# Argo2_Tracker.net
KiCad netlist of a schematic drawn in EAGLE
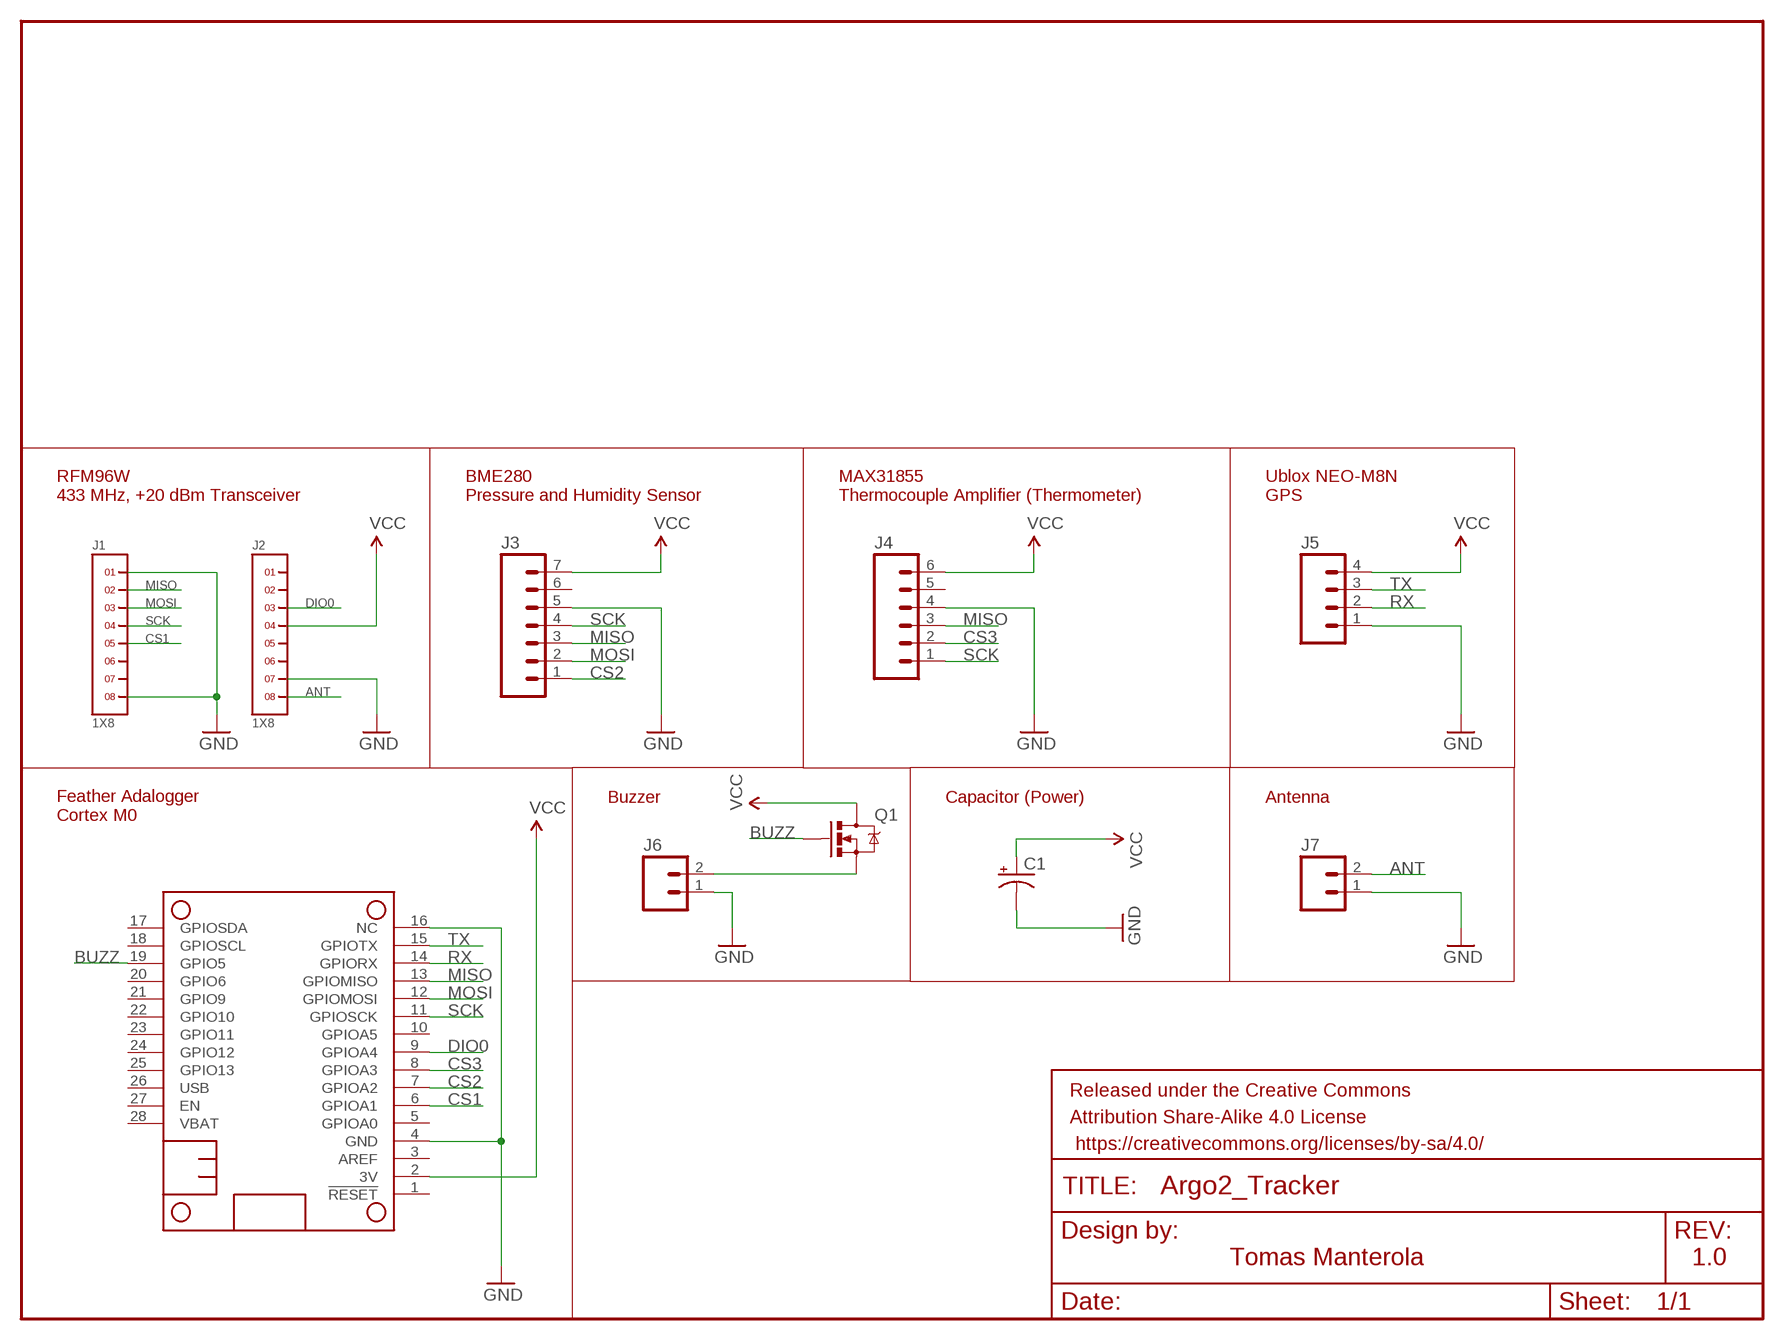
[diagram p0: schematic, sheet 1]

(export (version "E")
  (design (tool "Eeschema 10.0.6"))
  (components
    (comp (ref "C1")
      (value "CAP_POLPTH4")
      (footprint "eagle-import:CPOL-RADIAL-1000UF-25V")
      (libsource (lib "eagle-import") (part "CAP_POLPTH4"))
    )
    (comp (ref "FRAME1")
      (value "FRAME-LETTERNO_PACKAGE")
      (footprint "eagle-import:DUMMY")
      (fields (field (name "DESIGNER") "Tomas Manterola") (field (name "VERSION") "1.0"))
      (libsource (lib "eagle-import") (part "FRAME-LETTERNO_PACKAGE"))
    )
    (comp (ref "J1")
      (value "1X8")
      (footprint "eagle-import:1X8")
      (libsource (lib "eagle-import") (part "1X8"))
    )
    (comp (ref "J2")
      (value "1X8")
      (footprint "eagle-import:1X8")
      (libsource (lib "eagle-import") (part "1X8"))
    )
    (comp (ref "J3")
      (value "M07")
      (footprint "eagle-import:1X07")
      (libsource (lib "eagle-import") (part "M07"))
    )
    (comp (ref "J4")
      (value "M06SILK_FEMALE_PTH")
      (footprint "eagle-import:1X06")
      (libsource (lib "eagle-import") (part "M06SILK_FEMALE_PTH"))
    )
    (comp (ref "J5")
      (value "M041X04_NO_SILK")
      (footprint "eagle-import:1X04_NO_SILK")
      (libsource (lib "eagle-import") (part "M041X04_NO_SILK"))
    )
    (comp (ref "J6")
      (value "M02PTH")
      (footprint "eagle-import:1X02")
      (libsource (lib "eagle-import") (part "M02PTH"))
    )
    (comp (ref "J7")
      (value "M02PTH")
      (footprint "eagle-import:1X02")
      (libsource (lib "eagle-import") (part "M02PTH"))
    )
    (comp (ref "MS1")
      (value "FEATHERWING_NODIM")
      (footprint "eagle-import:FEATHERWING_DIM")
      (libsource (lib "eagle-import") (part "FEATHERWING_NODIM"))
    )
    (comp (ref "Q1")
      (value "MOSFET-NCHANNELFQP30N06L")
      (footprint "eagle-import:TO220V")
      (libsource (lib "eagle-import") (part "MOSFET-NCHANNELFQP30N06L"))
    )
  )
  (nets
    (net (code "1") (name "/ANT") (class "Default")
      (node (ref "J2") (pin "8") (pinfunction "8_8") (pintype "bidirectional"))
      (node (ref "J7") (pin "2") (pinfunction "2_2") (pintype "passive"))
    )
    (net (code "2") (name "/BUZZ") (class "Default")
      (node (ref "MS1") (pin "19") (pinfunction "GPIO5_19") (pintype "bidirectional"))
      (node (ref "Q1") (pin "1") (pinfunction "G_1") (pintype "passive"))
    )
    (net (code "3") (name "/CS1") (class "Default")
      (node (ref "J1") (pin "5") (pinfunction "5_5") (pintype "bidirectional"))
      (node (ref "MS1") (pin "6") (pinfunction "GPIOA1_6") (pintype "bidirectional"))
    )
    (net (code "4") (name "/CS2") (class "Default")
      (node (ref "J3") (pin "1") (pinfunction "1_1") (pintype "passive"))
      (node (ref "MS1") (pin "7") (pinfunction "GPIOA2_7") (pintype "bidirectional"))
    )
    (net (code "5") (name "/CS3") (class "Default")
      (node (ref "J4") (pin "2") (pinfunction "2_2") (pintype "passive"))
      (node (ref "MS1") (pin "8") (pinfunction "GPIOA3_8") (pintype "bidirectional"))
    )
    (net (code "6") (name "/DIO0") (class "Default")
      (node (ref "J2") (pin "3") (pinfunction "3_3") (pintype "bidirectional"))
      (node (ref "MS1") (pin "9") (pinfunction "GPIOA4_9") (pintype "bidirectional"))
    )
    (net (code "7") (name "/MISO") (class "Default")
      (node (ref "J1") (pin "2") (pinfunction "2_2") (pintype "bidirectional"))
      (node (ref "J3") (pin "3") (pinfunction "3_3") (pintype "passive"))
      (node (ref "J4") (pin "3") (pinfunction "3_3") (pintype "passive"))
      (node (ref "MS1") (pin "13") (pinfunction "GPIOMISO_13") (pintype "bidirectional"))
    )
    (net (code "8") (name "/MOSI") (class "Default")
      (node (ref "J1") (pin "3") (pinfunction "3_3") (pintype "bidirectional"))
      (node (ref "J3") (pin "2") (pinfunction "2_2") (pintype "passive"))
      (node (ref "MS1") (pin "12") (pinfunction "GPIOMOSI_12") (pintype "bidirectional"))
    )
    (net (code "9") (name "/RX") (class "Default")
      (node (ref "J5") (pin "2") (pinfunction "2_2") (pintype "passive"))
      (node (ref "MS1") (pin "14") (pinfunction "GPIORX_14") (pintype "bidirectional"))
    )
    (net (code "10") (name "/SCK") (class "Default")
      (node (ref "J1") (pin "4") (pinfunction "4_4") (pintype "bidirectional"))
      (node (ref "J3") (pin "4") (pinfunction "4_4") (pintype "passive"))
      (node (ref "J4") (pin "1") (pinfunction "1_1") (pintype "passive"))
      (node (ref "MS1") (pin "11") (pinfunction "GPIOSCK_11") (pintype "bidirectional"))
    )
    (net (code "11") (name "/TX") (class "Default")
      (node (ref "J5") (pin "3") (pinfunction "3_3") (pintype "passive"))
      (node (ref "MS1") (pin "15") (pinfunction "GPIOTX_15") (pintype "bidirectional"))
    )
    (net (code "12") (name "/USB") (class "Default")
      (node (ref "MS1") (pin "26") (pinfunction "USB_26") (pintype "power_in"))
    )
    (net (code "13") (name "/VBAT") (class "Default")
      (node (ref "MS1") (pin "28") (pinfunction "VBAT_28") (pintype "power_in"))
    )
    (net (code "14") (name "GND") (class "Default")
      (node (ref "C1") (pin "2") (pinfunction "-_2") (pintype "passive"))
      (node (ref "J1") (pin "1") (pinfunction "1_1") (pintype "bidirectional"))
      (node (ref "J1") (pin "8") (pinfunction "8_8") (pintype "bidirectional"))
      (node (ref "J2") (pin "7") (pinfunction "7_7") (pintype "bidirectional"))
      (node (ref "J3") (pin "5") (pinfunction "5_5") (pintype "passive"))
      (node (ref "J4") (pin "4") (pinfunction "4_4") (pintype "passive"))
      (node (ref "J5") (pin "1") (pinfunction "1_1") (pintype "passive"))
      (node (ref "J6") (pin "1") (pinfunction "1_1") (pintype "passive"))
      (node (ref "J7") (pin "1") (pinfunction "1_1") (pintype "passive"))
      (node (ref "MS1") (pin "16") (pinfunction "NC_16") (pintype "passive"))
      (node (ref "MS1") (pin "4") (pinfunction "GND_4") (pintype "power_in"))
    )
    (net (code "15") (name "Net-(Q1-S)") (class "Default")
      (node (ref "J6") (pin "2") (pinfunction "2_2") (pintype "passive"))
      (node (ref "Q1") (pin "3") (pinfunction "S_3") (pintype "passive"))
    )
    (net (code "16") (name "VCC") (class "Default")
      (node (ref "C1") (pin "1") (pinfunction "+_1") (pintype "passive"))
      (node (ref "J2") (pin "4") (pinfunction "4_4") (pintype "bidirectional"))
      (node (ref "J3") (pin "7") (pinfunction "7_7") (pintype "passive"))
      (node (ref "J4") (pin "6") (pinfunction "6_6") (pintype "passive"))
      (node (ref "J5") (pin "4") (pinfunction "4_4") (pintype "passive"))
      (node (ref "MS1") (pin "2") (pinfunction "3V_2") (pintype "power_in"))
      (node (ref "Q1") (pin "2") (pinfunction "D_2") (pintype "passive"))
    )
    (net (code "17") (name "unconnected-(J1-Pad6)") (class "Default")
      (node (ref "J1") (pin "6") (pinfunction "6_6") (pintype "bidirectional"))
    )
    (net (code "18") (name "unconnected-(J1-Pad7)") (class "Default")
      (node (ref "J1") (pin "7") (pinfunction "7_7") (pintype "bidirectional"))
    )
    (net (code "19") (name "unconnected-(J2-Pad1)") (class "Default")
      (node (ref "J2") (pin "1") (pinfunction "1_1") (pintype "bidirectional"))
    )
    (net (code "20") (name "unconnected-(J2-Pad2)") (class "Default")
      (node (ref "J2") (pin "2") (pinfunction "2_2") (pintype "bidirectional"))
    )
    (net (code "21") (name "unconnected-(J2-Pad5)") (class "Default")
      (node (ref "J2") (pin "5") (pinfunction "5_5") (pintype "bidirectional"))
    )
    (net (code "22") (name "unconnected-(J2-Pad6)") (class "Default")
      (node (ref "J2") (pin "6") (pinfunction "6_6") (pintype "bidirectional"))
    )
    (net (code "23") (name "unconnected-(J3-Pad6)") (class "Default")
      (node (ref "J3") (pin "6") (pinfunction "6_6") (pintype "passive"))
    )
    (net (code "24") (name "unconnected-(J4-Pad5)") (class "Default")
      (node (ref "J4") (pin "5") (pinfunction "5_5") (pintype "passive"))
    )
    (net (code "25") (name "unconnected-(MS1-AREF-Pad3)") (class "Default")
      (node (ref "MS1") (pin "3") (pinfunction "AREF_3") (pintype "passive"))
    )
    (net (code "26") (name "unconnected-(MS1-EN-Pad27)") (class "Default")
      (node (ref "MS1") (pin "27") (pinfunction "EN_27") (pintype "passive"))
    )
    (net (code "27") (name "unconnected-(MS1-GPIO6-Pad20)") (class "Default")
      (node (ref "MS1") (pin "20") (pinfunction "GPIO6_20") (pintype "bidirectional"))
    )
    (net (code "28") (name "unconnected-(MS1-GPIO9-Pad21)") (class "Default")
      (node (ref "MS1") (pin "21") (pinfunction "GPIO9_21") (pintype "bidirectional"))
    )
    (net (code "29") (name "unconnected-(MS1-GPIO10-Pad22)") (class "Default")
      (node (ref "MS1") (pin "22") (pinfunction "GPIO10_22") (pintype "bidirectional"))
    )
    (net (code "30") (name "unconnected-(MS1-GPIO11-Pad23)") (class "Default")
      (node (ref "MS1") (pin "23") (pinfunction "GPIO11_23") (pintype "bidirectional"))
    )
    (net (code "31") (name "unconnected-(MS1-GPIO12-Pad24)") (class "Default")
      (node (ref "MS1") (pin "24") (pinfunction "GPIO12_24") (pintype "bidirectional"))
    )
    (net (code "32") (name "unconnected-(MS1-GPIO13-Pad25)") (class "Default")
      (node (ref "MS1") (pin "25") (pinfunction "GPIO13_25") (pintype "bidirectional"))
    )
    (net (code "33") (name "unconnected-(MS1-GPIOA0-Pad5)") (class "Default")
      (node (ref "MS1") (pin "5") (pinfunction "GPIOA0_5") (pintype "bidirectional"))
    )
    (net (code "34") (name "unconnected-(MS1-GPIOA5-Pad10)") (class "Default")
      (node (ref "MS1") (pin "10") (pinfunction "GPIOA5_10") (pintype "bidirectional"))
    )
    (net (code "35") (name "unconnected-(MS1-GPIOSCL-Pad18)") (class "Default")
      (node (ref "MS1") (pin "18") (pinfunction "GPIOSCL_18") (pintype "bidirectional"))
    )
    (net (code "36") (name "unconnected-(MS1-GPIOSDA-Pad17)") (class "Default")
      (node (ref "MS1") (pin "17") (pinfunction "GPIOSDA_17") (pintype "bidirectional"))
    )
    (net (code "37") (name "unconnected-(MS1-~{RESET}-Pad1)") (class "Default")
      (node (ref "MS1") (pin "1") (pinfunction "~{RESET}_1") (pintype "input"))
    )
  )
)
